# bluetooth-buddy.net
KiCad netlist of a schematic drawn in EAGLE
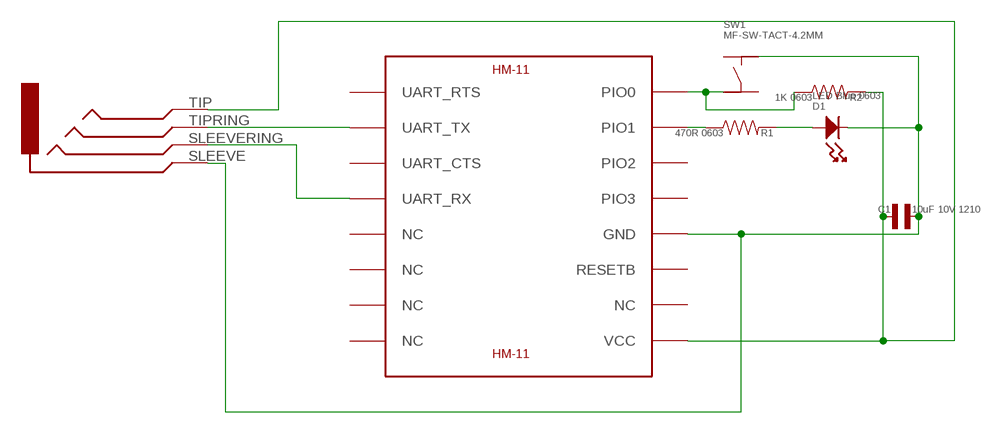
[diagram p0: schematic, sheet 1]

(export (version "E")
  (design (tool "Eeschema 10.0.6"))
  (components
    (comp (ref "C1")
      (value "10uF 10V 1210")
      (footprint "eagle-import:C1210")
      (libsource (lib "eagle-import") (part "CAPACITOR_NP_1210"))
    )
    (comp (ref "D1")
      (value "LED Blue 0603")
      (footprint "eagle-import:LED0603")
      (fields (field (name "HOUSEPART") "NO"))
      (libsource (lib "eagle-import") (part "LED_SINGLE-0603"))
    )
    (comp (ref "J1")
      (value "54-00035")
      (footprint "eagle-import:54-00035")
      (libsource (lib "eagle-import") (part "TRRS_JACK"))
    )
    (comp (ref "R1")
      (value "470R 0603")
      (footprint "eagle-import:R0603")
      (libsource (lib "eagle-import") (part "RESISTOR_0603"))
    )
    (comp (ref "R2")
      (value "1K 0603")
      (footprint "eagle-import:R0603")
      (libsource (lib "eagle-import") (part "RESISTOR_0603"))
    )
    (comp (ref "SW1")
      (value "MF-SW-TACT-4.2MM")
      (footprint "eagle-import:TACT4.2MM")
      (fields (field (name "HOUSEPART") "YES"))
      (libsource (lib "eagle-import") (part "TACT_4.2MM"))
    )
    (comp (ref "U$1")
      (value "HM-11")
      (footprint "eagle-import:HM-11")
      (libsource (lib "eagle-import") (part "HM-11"))
    )
  )
  (nets
    (net (code "1") (name "Net-(D1-PadANODE)") (class "Default")
      (node (ref "D1") (pin "ANODE") (pinfunction "ANODE_ANODE") (pintype "power_in"))
      (node (ref "R1") (pin "P$2") (pinfunction "P$2_P$2") (pintype "passive"))
    )
    (net (code "2") (name "Net-(J1-RS)") (class "Default")
      (node (ref "J1") (pin "SLEEVERING") (pinfunction "RS_SLEEVERING") (pintype "bidirectional"))
      (node (ref "U$1") (pin "UART_RX") (pinfunction "UART_RX_UART_RX") (pintype "bidirectional"))
    )
    (net (code "3") (name "Net-(J1-RT)") (class "Default")
      (node (ref "J1") (pin "TIPRING") (pinfunction "RT_TIPRING") (pintype "bidirectional"))
      (node (ref "U$1") (pin "UART_TX") (pinfunction "UART_TX_UART_TX") (pintype "bidirectional"))
    )
    (net (code "4") (name "Net-(J1-S)") (class "Default")
      (node (ref "C1") (pin "P$1") (pinfunction "P$1_P$1") (pintype "passive"))
      (node (ref "D1") (pin "CATHODE") (pinfunction "CATHODE_CATHODE") (pintype "power_in"))
      (node (ref "J1") (pin "SLEEVE") (pinfunction "S_SLEEVE") (pintype "bidirectional"))
      (node (ref "SW1") (pin "P$2") (pinfunction "P$2_P$2") (pintype "bidirectional"))
      (node (ref "U$1") (pin "GND") (pinfunction "GND_GND") (pintype "bidirectional"))
    )
    (net (code "5") (name "Net-(J1-T)") (class "Default")
      (node (ref "C1") (pin "P$2") (pinfunction "P$2_P$2") (pintype "passive"))
      (node (ref "J1") (pin "TIP") (pinfunction "T_TIP") (pintype "bidirectional"))
      (node (ref "R2") (pin "P$2") (pinfunction "P$2_P$2") (pintype "passive"))
      (node (ref "U$1") (pin "VCC") (pinfunction "VCC_VCC") (pintype "bidirectional"))
    )
    (net (code "6") (name "Net-(R1-PadP$1)") (class "Default")
      (node (ref "R1") (pin "P$1") (pinfunction "P$1_P$1") (pintype "passive"))
      (node (ref "U$1") (pin "PIO1") (pinfunction "PIO1_PIO1") (pintype "bidirectional"))
    )
    (net (code "7") (name "Net-(R2-PadP$1)") (class "Default")
      (node (ref "R2") (pin "P$1") (pinfunction "P$1_P$1") (pintype "passive"))
      (node (ref "SW1") (pin "P$3") (pinfunction "P$3_P$3") (pintype "bidirectional"))
      (node (ref "U$1") (pin "PIO0") (pinfunction "PIO0_PIO0") (pintype "bidirectional"))
    )
    (net (code "8") (name "unconnected-(SW1-PadP$1)") (class "Default")
      (node (ref "SW1") (pin "P$1") (pinfunction "P$1_P$1") (pintype "bidirectional"))
    )
    (net (code "9") (name "unconnected-(SW1-PadP$4)") (class "Default")
      (node (ref "SW1") (pin "P$4") (pinfunction "P$4_P$4") (pintype "bidirectional"))
    )
    (net (code "10") (name "unconnected-(U$1-NC-PadNC@5)") (class "Default")
      (node (ref "U$1") (pin "NC@5") (pinfunction "NC_NC@5") (pintype "bidirectional"))
    )
    (net (code "11") (name "unconnected-(U$1-NC-PadNC@6)") (class "Default")
      (node (ref "U$1") (pin "NC@6") (pinfunction "NC_NC@6") (pintype "bidirectional"))
    )
    (net (code "12") (name "unconnected-(U$1-NC-PadNC@7)") (class "Default")
      (node (ref "U$1") (pin "NC@7") (pinfunction "NC_NC@7") (pintype "bidirectional"))
    )
    (net (code "13") (name "unconnected-(U$1-NC-PadNC@8)") (class "Default")
      (node (ref "U$1") (pin "NC@8") (pinfunction "NC_NC@8") (pintype "bidirectional"))
    )
    (net (code "14") (name "unconnected-(U$1-NC-PadNC@10)") (class "Default")
      (node (ref "U$1") (pin "NC@10") (pinfunction "NC_NC@10") (pintype "bidirectional"))
    )
    (net (code "15") (name "unconnected-(U$1-PadPIO2)") (class "Default")
      (node (ref "U$1") (pin "PIO2") (pinfunction "PIO2_PIO2") (pintype "bidirectional"))
    )
    (net (code "16") (name "unconnected-(U$1-PadPIO3)") (class "Default")
      (node (ref "U$1") (pin "PIO3") (pinfunction "PIO3_PIO3") (pintype "bidirectional"))
    )
    (net (code "17") (name "unconnected-(U$1-PadRESETB)") (class "Default")
      (node (ref "U$1") (pin "RESETB") (pinfunction "RESETB_RESETB") (pintype "bidirectional"))
    )
    (net (code "18") (name "unconnected-(U$1-PadUART_CTS)") (class "Default")
      (node (ref "U$1") (pin "UART_CTS") (pinfunction "UART_CTS_UART_CTS") (pintype "bidirectional"))
    )
    (net (code "19") (name "unconnected-(U$1-PadUART_RTS)") (class "Default")
      (node (ref "U$1") (pin "UART_RTS") (pinfunction "UART_RTS_UART_RTS") (pintype "bidirectional"))
    )
  )
)
